# battery_timer.net
KiCad netlist of a schematic drawn in EAGLE
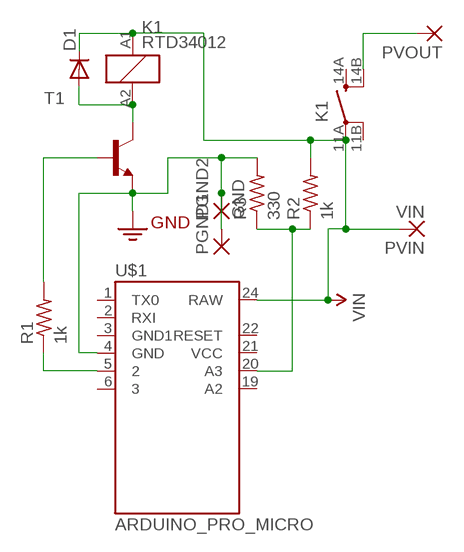
[diagram p0: schematic, sheet 1]

(export (version "E")
  (design (tool "Eeschema 10.0.6"))
  (components
    (comp (ref "D1")
      (value "DIODE-DO-214AC")
      (footprint "eagle-import:DO-214AC")
      (libsource (lib "eagle-import") (part "DIODE-DO-214AC"))
    )
    (comp (ref "K1")
      (value "RTD34012")
      (footprint "eagle-import:RT-N_O16A5")
      (fields (field (name "MF") "TYCO ELECTRONICS") (field (name "MPN") "RTD34012F"))
      (libsource (lib "eagle-import") (part "RTD34012"))
    )
    (comp (ref "PGND1")
      (value "SMD5")
      (footprint "eagle-import:SMD2,54-5,08")
      (libsource (lib "eagle-import") (part "SMD5"))
    )
    (comp (ref "PGND2")
      (value "GND")
      (footprint "eagle-import:SMD2,54-5,08")
      (libsource (lib "eagle-import") (part "SMD5"))
    )
    (comp (ref "PVIN")
      (value "VIN")
      (footprint "eagle-import:SMD2,54-5,08")
      (libsource (lib "eagle-import") (part "SMD5"))
    )
    (comp (ref "PVOUT")
      (value "SMD5")
      (footprint "eagle-import:SMD2,54-5,08")
      (libsource (lib "eagle-import") (part "SMD5"))
    )
    (comp (ref "R1")
      (value "1k")
      (footprint "eagle-import:R1206")
      (libsource (lib "eagle-import") (part "R-US_R1206"))
    )
    (comp (ref "R2")
      (value "1k")
      (footprint "eagle-import:R1206")
      (libsource (lib "eagle-import") (part "R-US_R1206"))
    )
    (comp (ref "R3")
      (value "330")
      (footprint "eagle-import:R1206")
      (libsource (lib "eagle-import") (part "R-US_R1206"))
    )
    (comp (ref "T1")
      (value "MMBT4401LT1-NPN-SOT23-BEC")
      (footprint "eagle-import:SOT23-BEC")
      (libsource (lib "eagle-import") (part "-NPN-SOT23-BECMMBT4401LT1"))
    )
    (comp (ref "U$1")
      (value "ARDUINO_PRO_MICRO")
      (footprint "eagle-import:ARDUINO_PRO_MICRO")
      (libsource (lib "eagle-import") (part "ARDUINO_PRO_MICRO"))
    )
  )
  (nets
    (net (code "1") (name "GND2") (class "Default")
      (node (ref "PGND1") (pin "1") (pinfunction "P_1") (pintype "passive"))
      (node (ref "PGND2") (pin "1") (pinfunction "P_1") (pintype "passive"))
      (node (ref "R3") (pin "2") (pinfunction "2_2") (pintype "passive"))
      (node (ref "T1") (pin "E") (pinfunction "E_E") (pintype "passive"))
      (node (ref "U$1") (pin "4") (pinfunction "GND_4") (pintype "bidirectional"))
    )
    (net (code "2") (name "Net-(K1A-2)") (class "Default")
      (node (ref "D1") (pin "A") (pinfunction "A_A") (pintype "passive"))
      (node (ref "K1") (pin "A2") (pinfunction "2_A2") (pintype "passive"))
      (node (ref "T1") (pin "C") (pinfunction "C_C") (pintype "passive"))
    )
    (net (code "3") (name "Net-(K1B-SB)") (class "Default")
      (node (ref "K1") (pin "14B") (pinfunction "SB_14B") (pintype "passive"))
      (node (ref "PVOUT") (pin "1") (pinfunction "P_1") (pintype "passive"))
    )
    (net (code "4") (name "Net-(R1-Pad2)") (class "Default")
      (node (ref "R1") (pin "2") (pinfunction "2_2") (pintype "passive"))
      (node (ref "T1") (pin "B") (pinfunction "B_B") (pintype "passive"))
    )
    (net (code "5") (name "Net-(U$1-2)") (class "Default")
      (node (ref "R1") (pin "1") (pinfunction "1_1") (pintype "passive"))
      (node (ref "U$1") (pin "5") (pinfunction "2_5") (pintype "bidirectional"))
    )
    (net (code "6") (name "Net-(U$1-A3)") (class "Default")
      (node (ref "R2") (pin "1") (pinfunction "1_1") (pintype "passive"))
      (node (ref "R3") (pin "1") (pinfunction "1_1") (pintype "passive"))
      (node (ref "U$1") (pin "20") (pinfunction "A3_20") (pintype "bidirectional"))
    )
    (net (code "7") (name "VIN") (class "Default")
      (node (ref "D1") (pin "C") (pinfunction "C_C") (pintype "passive"))
      (node (ref "K1") (pin "11A") (pinfunction "PA_11A") (pintype "passive"))
      (node (ref "K1") (pin "A1") (pinfunction "1_A1") (pintype "passive"))
      (node (ref "PVIN") (pin "1") (pinfunction "P_1") (pintype "passive"))
      (node (ref "R2") (pin "2") (pinfunction "2_2") (pintype "passive"))
      (node (ref "U$1") (pin "24") (pinfunction "RAW_24") (pintype "bidirectional"))
    )
    (net (code "8") (name "unconnected-(K1B-PB-Pad11B)") (class "Default")
      (node (ref "K1") (pin "11B") (pinfunction "PB_11B") (pintype "passive"))
    )
    (net (code "9") (name "unconnected-(K1B-SA-Pad14A)") (class "Default")
      (node (ref "K1") (pin "14A") (pinfunction "SA_14A") (pintype "passive"))
    )
    (net (code "10") (name "unconnected-(U$1-3-Pad6)") (class "Default")
      (node (ref "U$1") (pin "6") (pinfunction "3_6") (pintype "bidirectional"))
    )
    (net (code "11") (name "unconnected-(U$1-A2-Pad19)") (class "Default")
      (node (ref "U$1") (pin "19") (pinfunction "A2_19") (pintype "bidirectional"))
    )
    (net (code "12") (name "unconnected-(U$1-GND1-Pad3)") (class "Default")
      (node (ref "U$1") (pin "3") (pinfunction "GND1_3") (pintype "bidirectional"))
    )
    (net (code "13") (name "unconnected-(U$1-RESET-Pad22)") (class "Default")
      (node (ref "U$1") (pin "22") (pinfunction "RESET_22") (pintype "bidirectional"))
    )
    (net (code "14") (name "unconnected-(U$1-RXI-Pad2)") (class "Default")
      (node (ref "U$1") (pin "2") (pinfunction "RXI_2") (pintype "bidirectional"))
    )
    (net (code "15") (name "unconnected-(U$1-TX0-Pad1)") (class "Default")
      (node (ref "U$1") (pin "1") (pinfunction "TX0_1") (pintype "bidirectional"))
    )
    (net (code "16") (name "unconnected-(U$1-VCC-Pad21)") (class "Default")
      (node (ref "U$1") (pin "21") (pinfunction "VCC_21") (pintype "bidirectional"))
    )
  )
)
